# SCH_Smart-circular-LED-Lamp-PCB_2025-01-.net
KiCad netlist of a schematic drawn in EasyEDA
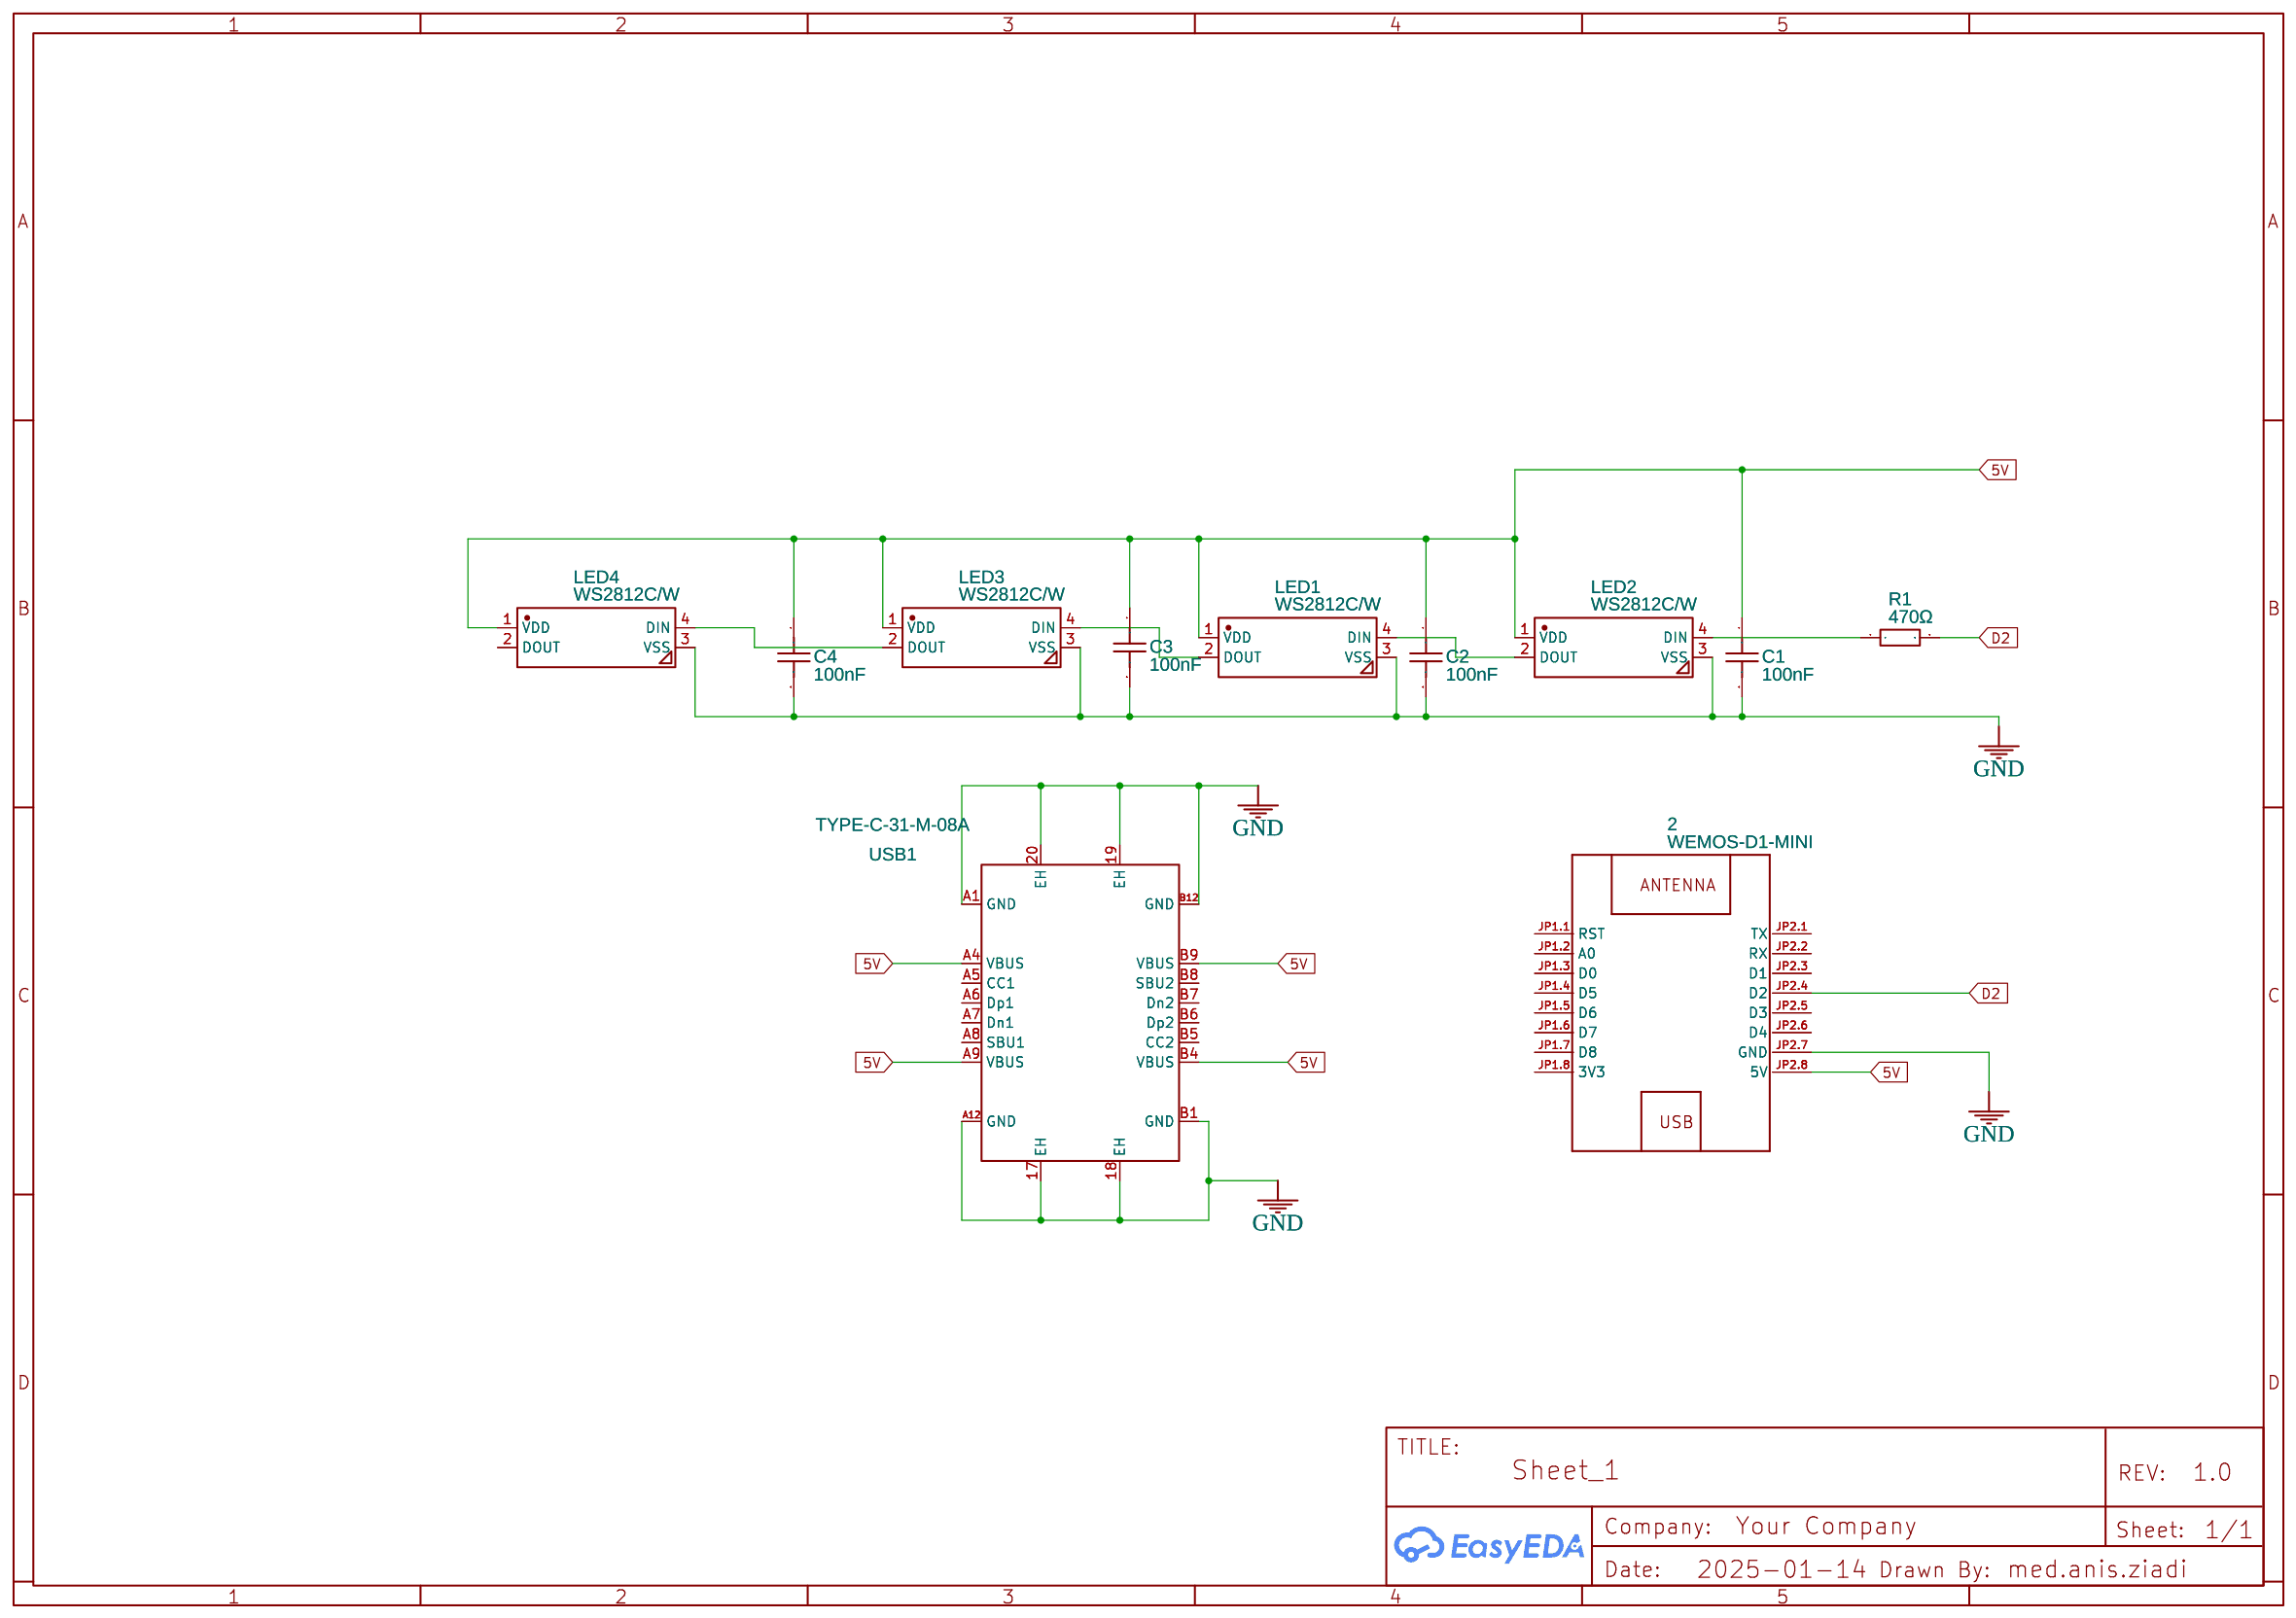
[diagram p0: schematic sheet]

(export (version "E")
  (design (tool "Eeschema 10.0.6"))
  (components
    (comp (ref "2") (value "WEMOS-D1-MINI") (libsource (lib "") (part "WEMOS-D1-MINI")))
    (comp (ref "C1")
      (value "100nF")
      (fields
        (field (name "Manufacturer Part") "AC0603KRX7R8BB104")
        (field (name "Manufacturer") "YAGEO(国巨)")
      )
      (libsource (lib "") (part "AC0603KRX7R8BB104"))
    )
    (comp (ref "C2")
      (value "100nF")
      (fields
        (field (name "Manufacturer Part") "AC0603KRX7R8BB104")
        (field (name "Manufacturer") "YAGEO(国巨)")
      )
      (libsource (lib "") (part "AC0603KRX7R8BB104"))
    )
    (comp (ref "C3")
      (value "100nF")
      (fields
        (field (name "Manufacturer Part") "AC0603KRX7R8BB104")
        (field (name "Manufacturer") "YAGEO(国巨)")
      )
      (libsource (lib "") (part "AC0603KRX7R8BB104"))
    )
    (comp (ref "C4")
      (value "100nF")
      (fields
        (field (name "Manufacturer Part") "AC0603KRX7R8BB104")
        (field (name "Manufacturer") "YAGEO(国巨)")
      )
      (libsource (lib "") (part "AC0603KRX7R8BB104"))
    )
    (comp (ref "LED1")
      (value "WS2812C/W")
      (fields (field (name "Manufacturer") "worldsemi"))
      (libsource (lib "") (part "WS2812C/W"))
    )
    (comp (ref "LED2")
      (value "WS2812C/W")
      (fields (field (name "Manufacturer") "worldsemi"))
      (libsource (lib "") (part "WS2812C/W"))
    )
    (comp (ref "LED3")
      (value "WS2812C/W")
      (fields (field (name "Manufacturer") "worldsemi"))
      (libsource (lib "") (part "WS2812C/W"))
    )
    (comp (ref "LED4")
      (value "WS2812C/W")
      (fields (field (name "Manufacturer") "worldsemi"))
      (libsource (lib "") (part "WS2812C/W"))
    )
    (comp (ref "R1")
      (value "470Ω")
      (fields (field (name "Manufacturer Part") "CR0603JA0471G") (field (name "Manufacturer") "LIZ(丽智电子)"))
      (libsource (lib "") (part "CR0603JA0471G"))
    )
    (comp (ref "USB1")
      (value "TYPE-C-31-M-08A")
      (fields (field (name "Manufacturer") "韩国韩荣"))
      (libsource (lib "") (part "TYPE-C-31-M-08A"))
    )
  )
  (nets
    (net (code "1") (name "5V") (class "Default")
      (node (ref "2") (pin "JP2.8") (pinfunction "5V_JP2.8") (pintype "bidirectional"))
      (node (ref "C1") (pin "1") (pinfunction "1_1") (pintype "unspecified"))
      (node (ref "C2") (pin "1") (pinfunction "1_1") (pintype "unspecified"))
      (node (ref "C3") (pin "1") (pinfunction "1_1") (pintype "unspecified"))
      (node (ref "C4") (pin "1") (pinfunction "1_1") (pintype "unspecified"))
      (node (ref "LED1") (pin "1") (pinfunction "VDD_1") (pintype "unspecified"))
      (node (ref "LED2") (pin "1") (pinfunction "VDD_1") (pintype "unspecified"))
      (node (ref "LED3") (pin "1") (pinfunction "VDD_1") (pintype "unspecified"))
      (node (ref "LED4") (pin "1") (pinfunction "VDD_1") (pintype "unspecified"))
      (node (ref "USB1") (pin "A4") (pinfunction "VBUS_A4") (pintype "unspecified"))
      (node (ref "USB1") (pin "A9") (pinfunction "VBUS_A9") (pintype "unspecified"))
      (node (ref "USB1") (pin "B4") (pinfunction "VBUS_B4") (pintype "unspecified"))
      (node (ref "USB1") (pin "B9") (pinfunction "VBUS_B9") (pintype "unspecified"))
    )
    (net (code "2") (name "D2") (class "Default")
      (node (ref "2") (pin "JP2.4") (pinfunction "D2_JP2.4") (pintype "bidirectional"))
      (node (ref "R1") (pin "2") (pinfunction "2_2") (pintype "input"))
    )
    (net (code "3") (name "GND") (class "Default")
      (node (ref "2") (pin "JP2.7") (pinfunction "GND_JP2.7") (pintype "bidirectional"))
      (node (ref "C1") (pin "2") (pinfunction "2_2") (pintype "unspecified"))
      (node (ref "C2") (pin "2") (pinfunction "2_2") (pintype "unspecified"))
      (node (ref "C3") (pin "2") (pinfunction "2_2") (pintype "unspecified"))
      (node (ref "C4") (pin "2") (pinfunction "2_2") (pintype "unspecified"))
      (node (ref "LED1") (pin "3") (pinfunction "VSS_3") (pintype "unspecified"))
      (node (ref "LED2") (pin "3") (pinfunction "VSS_3") (pintype "unspecified"))
      (node (ref "LED3") (pin "3") (pinfunction "VSS_3") (pintype "unspecified"))
      (node (ref "LED4") (pin "3") (pinfunction "VSS_3") (pintype "unspecified"))
      (node (ref "USB1") (pin "17") (pinfunction "EH_17") (pintype "unspecified"))
      (node (ref "USB1") (pin "18") (pinfunction "EH_18") (pintype "unspecified"))
      (node (ref "USB1") (pin "19") (pinfunction "EH_19") (pintype "unspecified"))
      (node (ref "USB1") (pin "20") (pinfunction "EH_20") (pintype "unspecified"))
      (node (ref "USB1") (pin "A1") (pinfunction "GND_A1") (pintype "unspecified"))
      (node (ref "USB1") (pin "A12") (pinfunction "GND_A12") (pintype "unspecified"))
      (node (ref "USB1") (pin "B1") (pinfunction "GND_B1") (pintype "unspecified"))
      (node (ref "USB1") (pin "B12") (pinfunction "GND_B12") (pintype "unspecified"))
    )
    (net (code "4") (name "Net-(LED1-DIN)") (class "Default")
      (node (ref "LED1") (pin "4") (pinfunction "DIN_4") (pintype "unspecified"))
      (node (ref "LED2") (pin "2") (pinfunction "DOUT_2") (pintype "unspecified"))
    )
    (net (code "5") (name "Net-(LED1-DOUT)") (class "Default")
      (node (ref "LED1") (pin "2") (pinfunction "DOUT_2") (pintype "unspecified"))
      (node (ref "LED3") (pin "4") (pinfunction "DIN_4") (pintype "unspecified"))
    )
    (net (code "6") (name "Net-(LED2-DIN)") (class "Default")
      (node (ref "LED2") (pin "4") (pinfunction "DIN_4") (pintype "unspecified"))
      (node (ref "R1") (pin "1") (pinfunction "1_1") (pintype "input"))
    )
    (net (code "7") (name "Net-(LED3-DOUT)") (class "Default")
      (node (ref "LED3") (pin "2") (pinfunction "DOUT_2") (pintype "unspecified"))
      (node (ref "LED4") (pin "4") (pinfunction "DIN_4") (pintype "unspecified"))
    )
    (net (code "8") (name "unconnected-(2-3V3-PadJP1.8)") (class "Default")
      (node (ref "2") (pin "JP1.8") (pinfunction "3V3_JP1.8") (pintype "bidirectional"))
    )
    (net (code "9") (name "unconnected-(2-A0-PadJP1.2)") (class "Default")
      (node (ref "2") (pin "JP1.2") (pinfunction "A0_JP1.2") (pintype "bidirectional"))
    )
    (net (code "10") (name "unconnected-(2-D0-PadJP1.3)") (class "Default")
      (node (ref "2") (pin "JP1.3") (pinfunction "D0_JP1.3") (pintype "bidirectional"))
    )
    (net (code "11") (name "unconnected-(2-D1-PadJP2.3)") (class "Default")
      (node (ref "2") (pin "JP2.3") (pinfunction "D1_JP2.3") (pintype "bidirectional"))
    )
    (net (code "12") (name "unconnected-(2-D3-PadJP2.5)") (class "Default")
      (node (ref "2") (pin "JP2.5") (pinfunction "D3_JP2.5") (pintype "bidirectional"))
    )
    (net (code "13") (name "unconnected-(2-D4-PadJP2.6)") (class "Default")
      (node (ref "2") (pin "JP2.6") (pinfunction "D4_JP2.6") (pintype "bidirectional"))
    )
    (net (code "14") (name "unconnected-(2-D5-PadJP1.4)") (class "Default")
      (node (ref "2") (pin "JP1.4") (pinfunction "D5_JP1.4") (pintype "bidirectional"))
    )
    (net (code "15") (name "unconnected-(2-D6-PadJP1.5)") (class "Default")
      (node (ref "2") (pin "JP1.5") (pinfunction "D6_JP1.5") (pintype "bidirectional"))
    )
    (net (code "16") (name "unconnected-(2-D7-PadJP1.6)") (class "Default")
      (node (ref "2") (pin "JP1.6") (pinfunction "D7_JP1.6") (pintype "bidirectional"))
    )
    (net (code "17") (name "unconnected-(2-D8-PadJP1.7)") (class "Default")
      (node (ref "2") (pin "JP1.7") (pinfunction "D8_JP1.7") (pintype "bidirectional"))
    )
    (net (code "18") (name "unconnected-(2-RST-PadJP1.1)") (class "Default")
      (node (ref "2") (pin "JP1.1") (pinfunction "RST_JP1.1") (pintype "bidirectional"))
    )
    (net (code "19") (name "unconnected-(2-RX-PadJP2.2)") (class "Default")
      (node (ref "2") (pin "JP2.2") (pinfunction "RX_JP2.2") (pintype "bidirectional"))
    )
    (net (code "20") (name "unconnected-(2-TX-PadJP2.1)") (class "Default")
      (node (ref "2") (pin "JP2.1") (pinfunction "TX_JP2.1") (pintype "bidirectional"))
    )
    (net (code "21") (name "unconnected-(LED4-DOUT-Pad2)") (class "Default")
      (node (ref "LED4") (pin "2") (pinfunction "DOUT_2") (pintype "unspecified"))
    )
    (net (code "22") (name "unconnected-(USB1-CC1-PadA5)") (class "Default")
      (node (ref "USB1") (pin "A5") (pinfunction "CC1_A5") (pintype "unspecified"))
    )
    (net (code "23") (name "unconnected-(USB1-CC2-PadB5)") (class "Default")
      (node (ref "USB1") (pin "B5") (pinfunction "CC2_B5") (pintype "unspecified"))
    )
    (net (code "24") (name "unconnected-(USB1-Dn1-PadA7)") (class "Default")
      (node (ref "USB1") (pin "A7") (pinfunction "Dn1_A7") (pintype "unspecified"))
    )
    (net (code "25") (name "unconnected-(USB1-Dn2-PadB7)") (class "Default")
      (node (ref "USB1") (pin "B7") (pinfunction "Dn2_B7") (pintype "unspecified"))
    )
    (net (code "26") (name "unconnected-(USB1-Dp1-PadA6)") (class "Default")
      (node (ref "USB1") (pin "A6") (pinfunction "Dp1_A6") (pintype "unspecified"))
    )
    (net (code "27") (name "unconnected-(USB1-Dp2-PadB6)") (class "Default")
      (node (ref "USB1") (pin "B6") (pinfunction "Dp2_B6") (pintype "unspecified"))
    )
    (net (code "28") (name "unconnected-(USB1-SBU1-PadA8)") (class "Default")
      (node (ref "USB1") (pin "A8") (pinfunction "SBU1_A8") (pintype "unspecified"))
    )
    (net (code "29") (name "unconnected-(USB1-SBU2-PadB8)") (class "Default")
      (node (ref "USB1") (pin "B8") (pinfunction "SBU2_B8") (pintype "unspecified"))
    )
  )
)
